# power.net
KiCad netlist of a schematic drawn in EAGLE
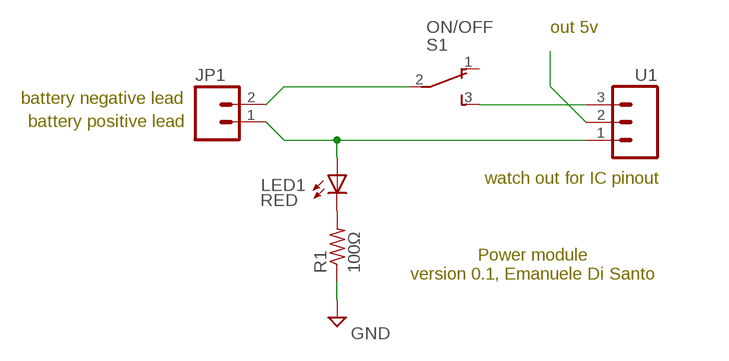
[diagram p0: schematic, sheet 1]

(export (version "E")
  (design (tool "Eeschema 10.0.6"))
  (components
    (comp (ref "JP1")
      (value "M02JST-PTH-2")
      (footprint "eagle-import:JST-2-PTH")
      (libsource (lib "eagle-import") (part "M02JST-PTH-2"))
    )
    (comp (ref "LED1")
      (value "RED")
      (footprint "eagle-import:CHIP-LED0805")
      (libsource (lib "eagle-import") (part "LEDCHIP-LED0805"))
    )
    (comp (ref "R1")
      (value "100Ω")
      (footprint "eagle-import:M3216")
      (libsource (lib "eagle-import") (part "R-US_M3216"))
    )
    (comp (ref "S1")
      (value "ON/OFF")
      (footprint "eagle-import:TL3XPO")
      (libsource (lib "eagle-import") (part "TL36PO"))
    )
    (comp (ref "U1")
      (value "M03PTH")
      (footprint "eagle-import:1X03")
      (libsource (lib "eagle-import") (part "M03PTH"))
    )
  )
  (nets
    (net (code "1") (name "GND") (class "Default")
      (node (ref "R1") (pin "1") (pinfunction "1_1") (pintype "passive"))
    )
    (net (code "2") (name "Net-(JP1-Pad1)") (class "Default")
      (node (ref "JP1") (pin "1") (pinfunction "1_1") (pintype "passive"))
      (node (ref "LED1") (pin "A") (pinfunction "A_A") (pintype "passive"))
      (node (ref "U1") (pin "1") (pinfunction "1_1") (pintype "passive"))
    )
    (net (code "3") (name "Net-(LED1-PadC)") (class "Default")
      (node (ref "LED1") (pin "C") (pinfunction "C_C") (pintype "passive"))
      (node (ref "R1") (pin "2") (pinfunction "2_2") (pintype "passive"))
    )
    (net (code "4") (name "Net-(S1-P)") (class "Default")
      (node (ref "JP1") (pin "2") (pinfunction "2_2") (pintype "passive"))
      (node (ref "S1") (pin "2") (pinfunction "P_2") (pintype "passive"))
    )
    (net (code "5") (name "Net-(S1-S)") (class "Default")
      (node (ref "S1") (pin "3") (pinfunction "S_3") (pintype "passive"))
      (node (ref "U1") (pin "3") (pinfunction "3_3") (pintype "passive"))
    )
    (net (code "6") (name "unconnected-(S1-O-Pad1)") (class "Default")
      (node (ref "S1") (pin "1") (pinfunction "O_1") (pintype "passive"))
    )
    (net (code "7") (name "unconnected-(U1-Pad2)") (class "Default")
      (node (ref "U1") (pin "2") (pinfunction "2_2") (pintype "passive"))
    )
  )
)
